# 3S2Pcard.net
KiCad netlist of a schematic drawn in EAGLE
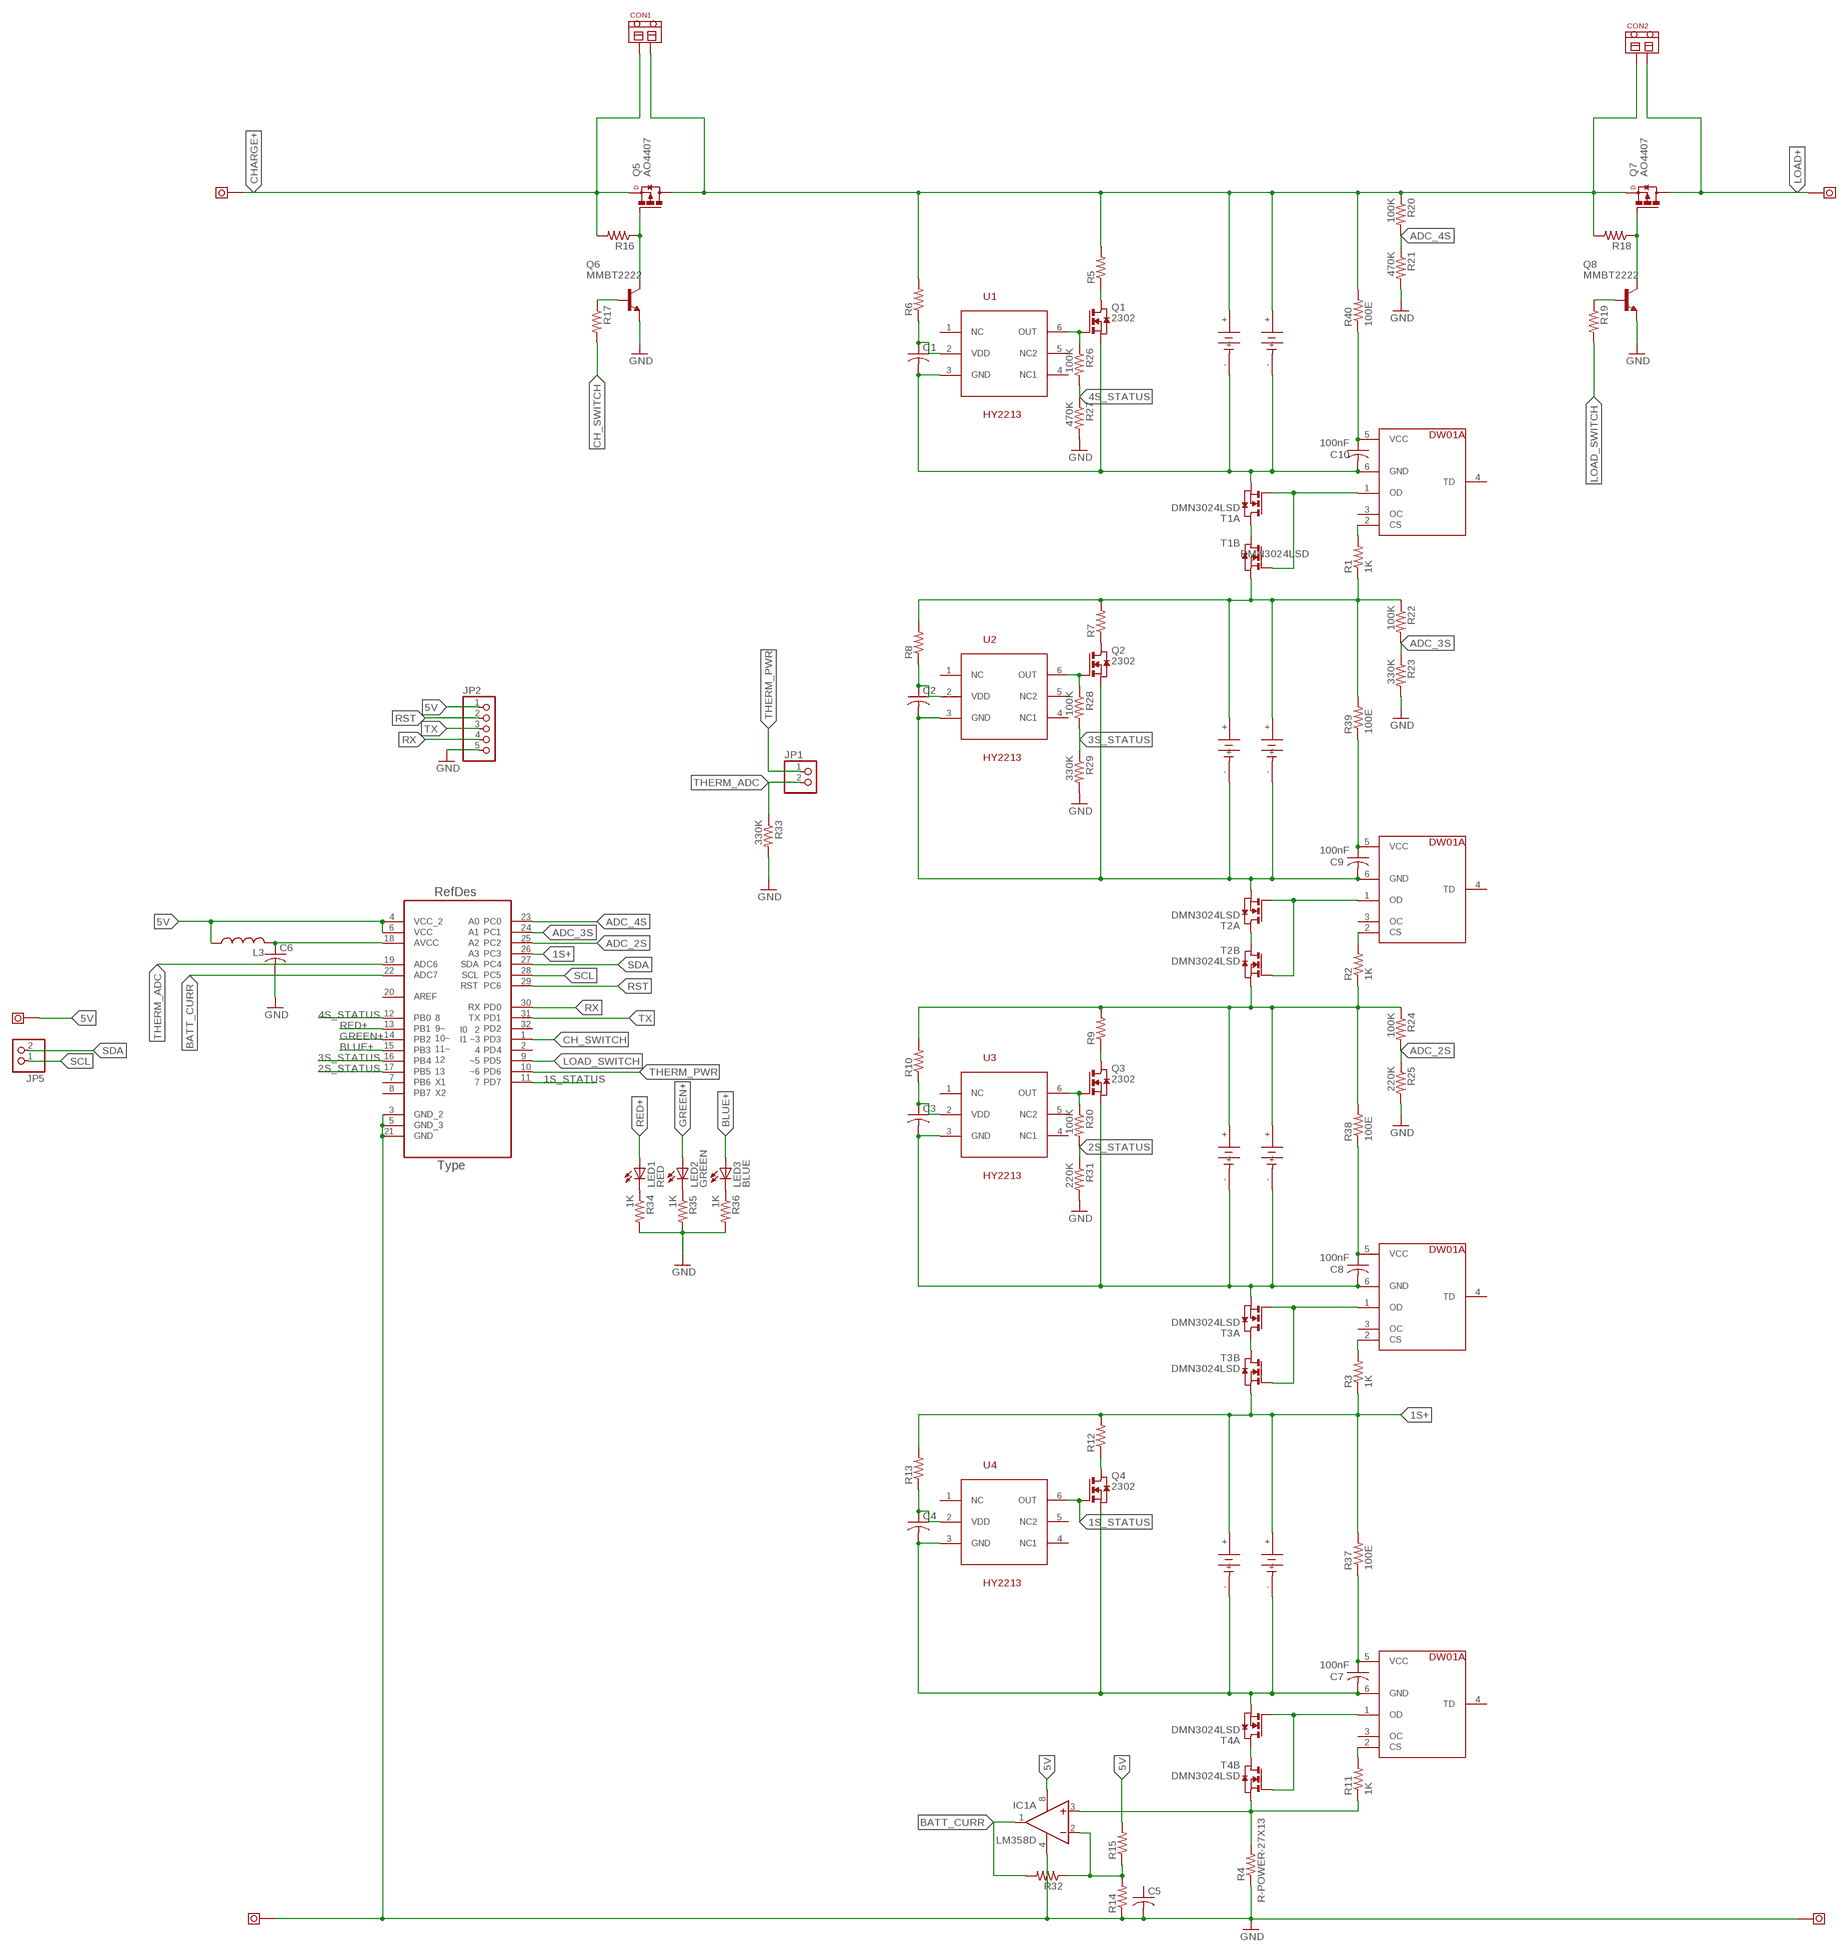
[diagram p0: schematic, sheet 1]

(export (version "E")
  (design (tool "Eeschema 10.0.6"))
  (components
    (comp (ref "B11")
      (value "18650_HOLDER")
      (footprint "eagle-import:18650_HOLDER")
      (libsource (lib "eagle-import") (part "18650_HOLDER"))
    )
    (comp (ref "B12")
      (value "18650_HOLDER")
      (footprint "eagle-import:18650_HOLDER")
      (libsource (lib "eagle-import") (part "18650_HOLDER"))
    )
    (comp (ref "B21")
      (value "18650_HOLDER")
      (footprint "eagle-import:18650_HOLDER")
      (libsource (lib "eagle-import") (part "18650_HOLDER"))
    )
    (comp (ref "B22")
      (value "18650_HOLDER")
      (footprint "eagle-import:18650_HOLDER")
      (libsource (lib "eagle-import") (part "18650_HOLDER"))
    )
    (comp (ref "B31")
      (value "18650_HOLDER")
      (footprint "eagle-import:18650_HOLDER")
      (libsource (lib "eagle-import") (part "18650_HOLDER"))
    )
    (comp (ref "B32")
      (value "18650_HOLDER")
      (footprint "eagle-import:18650_HOLDER")
      (libsource (lib "eagle-import") (part "18650_HOLDER"))
    )
    (comp (ref "B41")
      (value "18650_HOLDER")
      (footprint "eagle-import:18650_HOLDER")
      (libsource (lib "eagle-import") (part "18650_HOLDER"))
    )
    (comp (ref "B42")
      (value "18650_HOLDER")
      (footprint "eagle-import:18650_HOLDER")
      (libsource (lib "eagle-import") (part "18650_HOLDER"))
    )
    (comp (ref "C1")
      (value "C-USC0805")
      (footprint "eagle-import:C0805")
      (libsource (lib "eagle-import") (part "C-USC0805"))
    )
    (comp (ref "C2")
      (value "C-USC0805")
      (footprint "eagle-import:C0805")
      (libsource (lib "eagle-import") (part "C-USC0805"))
    )
    (comp (ref "C3")
      (value "C-USC0805")
      (footprint "eagle-import:C0805")
      (libsource (lib "eagle-import") (part "C-USC0805"))
    )
    (comp (ref "C4")
      (value "C-USC0805")
      (footprint "eagle-import:C0805")
      (libsource (lib "eagle-import") (part "C-USC0805"))
    )
    (comp (ref "C5")
      (value "C-USC0805")
      (footprint "eagle-import:C0805")
      (libsource (lib "eagle-import") (part "C-USC0805"))
    )
    (comp (ref "C6")
      (value "C-USC0805")
      (footprint "eagle-import:C0805")
      (libsource (lib "eagle-import") (part "C-USC0805"))
    )
    (comp (ref "C7")
      (value "100nF")
      (footprint "eagle-import:C0805")
      (libsource (lib "eagle-import") (part "C-USC0805"))
    )
    (comp (ref "C8")
      (value "100nF")
      (footprint "eagle-import:C0805")
      (libsource (lib "eagle-import") (part "C-USC0805"))
    )
    (comp (ref "C9")
      (value "100nF")
      (footprint "eagle-import:C0805")
      (libsource (lib "eagle-import") (part "C-USC0805"))
    )
    (comp (ref "C10")
      (value "100nF")
      (footprint "eagle-import:C0805")
      (libsource (lib "eagle-import") (part "C-USC0805"))
    )
    (comp (ref "CON1")
      (value "TERMINAL-SMALL")
      (footprint "eagle-import:TERMINAL-SMALL")
      (libsource (lib "eagle-import") (part "TERMINAL-SMALL"))
    )
    (comp (ref "CON2")
      (value "TERMINAL-SMALL")
      (footprint "eagle-import:TERMINAL-SMALL")
      (libsource (lib "eagle-import") (part "TERMINAL-SMALL"))
    )
    (comp (ref "IC1")
      (value "LM358D")
      (footprint "eagle-import:SO08")
      (libsource (lib "eagle-import") (part "LM358D"))
    )
    (comp (ref "JP1")
      (value "PINHD-1X2")
      (footprint "eagle-import:1X02")
      (libsource (lib "eagle-import") (part "PINHD-1X2"))
    )
    (comp (ref "JP2")
      (value "PINHD-1X5")
      (footprint "eagle-import:1X05")
      (libsource (lib "eagle-import") (part "PINHD-1X5"))
    )
    (comp (ref "JP5")
      (value "PINHD-1X2")
      (footprint "eagle-import:1X02")
      (libsource (lib "eagle-import") (part "PINHD-1X2"))
    )
    (comp (ref "L3")
      (value "L-US0207/10")
      (footprint "eagle-import:0207_10")
      (libsource (lib "eagle-import") (part "L-US0207/10"))
    )
    (comp (ref "LED1")
      (value "RED")
      (footprint "eagle-import:CHIP-LED0805")
      (libsource (lib "eagle-import") (part "LEDCHIP-LED0805"))
    )
    (comp (ref "LED2")
      (value "GREEN")
      (footprint "eagle-import:CHIP-LED0805")
      (libsource (lib "eagle-import") (part "LEDCHIP-LED0805"))
    )
    (comp (ref "LED3")
      (value "BLUE")
      (footprint "eagle-import:CHIP-LED0805")
      (libsource (lib "eagle-import") (part "LEDCHIP-LED0805"))
    )
    (comp (ref "Q1")
      (value "2302")
      (footprint "eagle-import:TO236")
      (libsource (lib "eagle-import") (part "2302"))
    )
    (comp (ref "Q2")
      (value "2302")
      (footprint "eagle-import:TO236")
      (libsource (lib "eagle-import") (part "2302"))
    )
    (comp (ref "Q3")
      (value "2302")
      (footprint "eagle-import:TO236")
      (libsource (lib "eagle-import") (part "2302"))
    )
    (comp (ref "Q4")
      (value "2302")
      (footprint "eagle-import:TO236")
      (libsource (lib "eagle-import") (part "2302"))
    )
    (comp (ref "Q5")
      (value "AO4407")
      (footprint "eagle-import:SOIC8")
      (libsource (lib "eagle-import") (part "AO4407"))
    )
    (comp (ref "Q6")
      (value "MMBT2222")
      (footprint "eagle-import:SOT-23-CBE")
      (libsource (lib "eagle-import") (part "MMBT2222"))
    )
    (comp (ref "Q7")
      (value "AO4407")
      (footprint "eagle-import:SOIC8")
      (libsource (lib "eagle-import") (part "AO4407"))
    )
    (comp (ref "Q8")
      (value "MMBT2222")
      (footprint "eagle-import:SOT-23-CBE")
      (libsource (lib "eagle-import") (part "MMBT2222"))
    )
    (comp (ref "R1")
      (value "1K")
      (footprint "eagle-import:R0805")
      (libsource (lib "eagle-import") (part "R-US_R0805"))
    )
    (comp (ref "R2")
      (value "1K")
      (footprint "eagle-import:R0805")
      (libsource (lib "eagle-import") (part "R-US_R0805"))
    )
    (comp (ref "R3")
      (value "1K")
      (footprint "eagle-import:R0805")
      (libsource (lib "eagle-import") (part "R-US_R0805"))
    )
    (comp (ref "R4")
      (value "R-POWER-27X13")
      (footprint "eagle-import:R-27X13")
      (libsource (lib "eagle-import") (part "R-POWER-27X13"))
    )
    (comp (ref "R5")
      (value "R-US_R1206W")
      (footprint "eagle-import:R1206W")
      (libsource (lib "eagle-import") (part "R-US_R1206W"))
    )
    (comp (ref "R6")
      (value "R-US_R0805")
      (footprint "eagle-import:R0805")
      (libsource (lib "eagle-import") (part "R-US_R0805"))
    )
    (comp (ref "R7")
      (value "R-US_R1206W")
      (footprint "eagle-import:R1206W")
      (libsource (lib "eagle-import") (part "R-US_R1206W"))
    )
    (comp (ref "R8")
      (value "R-US_R0805")
      (footprint "eagle-import:R0805")
      (libsource (lib "eagle-import") (part "R-US_R0805"))
    )
    (comp (ref "R9")
      (value "R-US_R1206W")
      (footprint "eagle-import:R1206W")
      (libsource (lib "eagle-import") (part "R-US_R1206W"))
    )
    (comp (ref "R10")
      (value "R-US_R0805")
      (footprint "eagle-import:R0805")
      (libsource (lib "eagle-import") (part "R-US_R0805"))
    )
    (comp (ref "R11")
      (value "1K")
      (footprint "eagle-import:R0805")
      (libsource (lib "eagle-import") (part "R-US_R0805"))
    )
    (comp (ref "R12")
      (value "R-US_R1206W")
      (footprint "eagle-import:R1206W")
      (libsource (lib "eagle-import") (part "R-US_R1206W"))
    )
    (comp (ref "R13")
      (value "R-US_R0805")
      (footprint "eagle-import:R0805")
      (libsource (lib "eagle-import") (part "R-US_R0805"))
    )
    (comp (ref "R14")
      (value "R-US_R0805")
      (footprint "eagle-import:R0805")
      (libsource (lib "eagle-import") (part "R-US_R0805"))
    )
    (comp (ref "R15")
      (value "R-US_R0805")
      (footprint "eagle-import:R0805")
      (libsource (lib "eagle-import") (part "R-US_R0805"))
    )
    (comp (ref "R16")
      (value "R-US_R0805")
      (footprint "eagle-import:R0805")
      (libsource (lib "eagle-import") (part "R-US_R0805"))
    )
    (comp (ref "R17")
      (value "R-US_R0805")
      (footprint "eagle-import:R0805")
      (libsource (lib "eagle-import") (part "R-US_R0805"))
    )
    (comp (ref "R18")
      (value "R-US_R0805")
      (footprint "eagle-import:R0805")
      (libsource (lib "eagle-import") (part "R-US_R0805"))
    )
    (comp (ref "R19")
      (value "R-US_R0805")
      (footprint "eagle-import:R0805")
      (libsource (lib "eagle-import") (part "R-US_R0805"))
    )
    (comp (ref "R20")
      (value "100K")
      (footprint "eagle-import:R0805")
      (libsource (lib "eagle-import") (part "R-US_R0805"))
    )
    (comp (ref "R21")
      (value "470K")
      (footprint "eagle-import:R0805")
      (libsource (lib "eagle-import") (part "R-US_R0805"))
    )
    (comp (ref "R22")
      (value "100K")
      (footprint "eagle-import:R0805")
      (libsource (lib "eagle-import") (part "R-US_R0805"))
    )
    (comp (ref "R23")
      (value "330K")
      (footprint "eagle-import:R0805")
      (libsource (lib "eagle-import") (part "R-US_R0805"))
    )
    (comp (ref "R24")
      (value "100K")
      (footprint "eagle-import:R0805")
      (libsource (lib "eagle-import") (part "R-US_R0805"))
    )
    (comp (ref "R25")
      (value "220K")
      (footprint "eagle-import:R0805")
      (libsource (lib "eagle-import") (part "R-US_R0805"))
    )
    (comp (ref "R26")
      (value "100K")
      (footprint "eagle-import:R0805")
      (libsource (lib "eagle-import") (part "R-US_R0805"))
    )
    (comp (ref "R27")
      (value "470K")
      (footprint "eagle-import:R0805")
      (libsource (lib "eagle-import") (part "R-US_R0805"))
    )
    (comp (ref "R28")
      (value "100K")
      (footprint "eagle-import:R0805")
      (libsource (lib "eagle-import") (part "R-US_R0805"))
    )
    (comp (ref "R29")
      (value "330K")
      (footprint "eagle-import:R0805")
      (libsource (lib "eagle-import") (part "R-US_R0805"))
    )
    (comp (ref "R30")
      (value "100K")
      (footprint "eagle-import:R0805")
      (libsource (lib "eagle-import") (part "R-US_R0805"))
    )
    (comp (ref "R31")
      (value "220K")
      (footprint "eagle-import:R0805")
      (libsource (lib "eagle-import") (part "R-US_R0805"))
    )
    (comp (ref "R32")
      (value "R-US_R0805")
      (footprint "eagle-import:R0805")
      (libsource (lib "eagle-import") (part "R-US_R0805"))
    )
    (comp (ref "R33")
      (value "330K")
      (footprint "eagle-import:R0805")
      (libsource (lib "eagle-import") (part "R-US_R0805"))
    )
    (comp (ref "R34")
      (value "1K")
      (footprint "eagle-import:R0805")
      (libsource (lib "eagle-import") (part "R-US_R0805"))
    )
    (comp (ref "R35")
      (value "1K")
      (footprint "eagle-import:R0805")
      (libsource (lib "eagle-import") (part "R-US_R0805"))
    )
    (comp (ref "R36")
      (value "1K")
      (footprint "eagle-import:R0805")
      (libsource (lib "eagle-import") (part "R-US_R0805"))
    )
    (comp (ref "R37")
      (value "100E")
      (footprint "eagle-import:R0805")
      (libsource (lib "eagle-import") (part "R-US_R0805"))
    )
    (comp (ref "R38")
      (value "100E")
      (footprint "eagle-import:R0805")
      (libsource (lib "eagle-import") (part "R-US_R0805"))
    )
    (comp (ref "R39")
      (value "100E")
      (footprint "eagle-import:R0805")
      (libsource (lib "eagle-import") (part "R-US_R0805"))
    )
    (comp (ref "R40")
      (value "100E")
      (footprint "eagle-import:R0805")
      (libsource (lib "eagle-import") (part "R-US_R0805"))
    )
    (comp (ref "T1")
      (value "DMN3024LSD")
      (footprint "eagle-import:TSSOP-8")
      (libsource (lib "eagle-import") (part "DMN3024LSD"))
    )
    (comp (ref "T2")
      (value "DMN3024LSD")
      (footprint "eagle-import:TSSOP-8")
      (libsource (lib "eagle-import") (part "DMN3024LSD"))
    )
    (comp (ref "T3")
      (value "DMN3024LSD")
      (footprint "eagle-import:TSSOP-8")
      (libsource (lib "eagle-import") (part "DMN3024LSD"))
    )
    (comp (ref "T4")
      (value "DMN3024LSD")
      (footprint "eagle-import:TSSOP-8")
      (libsource (lib "eagle-import") (part "DMN3024LSD"))
    )
    (comp (ref "U$7")
      (value "DW01A")
      (footprint "eagle-import:SOT23-6")
      (libsource (lib "eagle-import") (part "DW01A"))
    )
    (comp (ref "U$8")
      (value "DW01A")
      (footprint "eagle-import:SOT23-6")
      (libsource (lib "eagle-import") (part "DW01A"))
    )
    (comp (ref "U$9")
      (value "DW01A")
      (footprint "eagle-import:SOT23-6")
      (libsource (lib "eagle-import") (part "DW01A"))
    )
    (comp (ref "U$13")
      (value "METAL_SPACER")
      (footprint "eagle-import:SPACER")
      (libsource (lib "eagle-import") (part "METAL_SPACER"))
    )
    (comp (ref "U$14")
      (value "METAL_SPACER")
      (footprint "eagle-import:SPACER")
      (libsource (lib "eagle-import") (part "METAL_SPACER"))
    )
    (comp (ref "U$15")
      (value "METAL_SPACER")
      (footprint "eagle-import:SPACER")
      (libsource (lib "eagle-import") (part "METAL_SPACER"))
    )
    (comp (ref "U$16")
      (value "METAL_SPACER")
      (footprint "eagle-import:SPACER")
      (libsource (lib "eagle-import") (part "METAL_SPACER"))
    )
    (comp (ref "U$17")
      (value "METAL_SPACER")
      (footprint "eagle-import:SPACER")
      (libsource (lib "eagle-import") (part "METAL_SPACER"))
    )
    (comp (ref "U1")
      (value "HY2213")
      (footprint "eagle-import:SOT23-6")
      (libsource (lib "eagle-import") (part "HY2213"))
    )
    (comp (ref "U2")
      (value "HY2213")
      (footprint "eagle-import:SOT23-6")
      (libsource (lib "eagle-import") (part "HY2213"))
    )
    (comp (ref "U3")
      (value "HY2213")
      (footprint "eagle-import:SOT23-6")
      (libsource (lib "eagle-import") (part "HY2213"))
    )
    (comp (ref "U4")
      (value "HY2213")
      (footprint "eagle-import:SOT23-6")
      (libsource (lib "eagle-import") (part "HY2213"))
    )
    (comp (ref "U5")
      (value "ATMEGA328P-AU")
      (footprint "eagle-import:QFP80P900X900X120-32N")
      (libsource (lib "eagle-import") (part "ATMEGA328P-AU"))
    )
    (comp (ref "U12")
      (value "DW01A")
      (footprint "eagle-import:SOT23-6")
      (libsource (lib "eagle-import") (part "DW01A"))
    )
  )
  (nets
    (net (code "1") (name "1S+") (class "Default")
      (node (ref "B11") (pin "+") (pinfunction "+_+") (pintype "bidirectional"))
      (node (ref "B12") (pin "+") (pinfunction "+_+") (pintype "bidirectional"))
      (node (ref "R12") (pin "2") (pinfunction "2_2") (pintype "passive"))
      (node (ref "R13") (pin "2") (pinfunction "2_2") (pintype "passive"))
      (node (ref "R3") (pin "1") (pinfunction "1_1") (pintype "passive"))
      (node (ref "R37") (pin "2") (pinfunction "2_2") (pintype "passive"))
      (node (ref "T3") (pin "6") (pinfunction "S_6") (pintype "passive"))
      (node (ref "T3") (pin "7") (pinfunction "S_7") (pintype "passive"))
      (node (ref "U5") (pin "26") (pinfunction "PC3_26") (pintype "bidirectional"))
    )
    (net (code "2") (name "1S_STATUS") (class "Default")
      (node (ref "Q4") (pin "2") (pinfunction "G_2") (pintype "passive"))
      (node (ref "U4") (pin "6") (pinfunction "OUT_6") (pintype "bidirectional"))
      (node (ref "U5") (pin "11") (pinfunction "PD7_11") (pintype "bidirectional"))
    )
    (net (code "3") (name "2S_STATUS") (class "Default")
      (node (ref "R30") (pin "2") (pinfunction "2_2") (pintype "passive"))
      (node (ref "R31") (pin "1") (pinfunction "1_1") (pintype "passive"))
      (node (ref "U5") (pin "17") (pinfunction "PB5_17") (pintype "bidirectional"))
    )
    (net (code "4") (name "3S_STATUS") (class "Default")
      (node (ref "R28") (pin "2") (pinfunction "2_2") (pintype "passive"))
      (node (ref "R29") (pin "1") (pinfunction "1_1") (pintype "passive"))
      (node (ref "U5") (pin "16") (pinfunction "PB4_16") (pintype "bidirectional"))
    )
    (net (code "5") (name "4S_STATUS") (class "Default")
      (node (ref "R26") (pin "2") (pinfunction "2_2") (pintype "passive"))
      (node (ref "R27") (pin "1") (pinfunction "1_1") (pintype "passive"))
      (node (ref "U5") (pin "12") (pinfunction "PB0_12") (pintype "bidirectional"))
    )
    (net (code "6") (name "5V") (class "Default")
      (node (ref "IC1") (pin "8") (pinfunction "V+_8") (pintype "power_in"))
      (node (ref "JP2") (pin "1") (pinfunction "1_1") (pintype "passive"))
      (node (ref "L3") (pin "1") (pinfunction "1_1") (pintype "passive"))
      (node (ref "R15") (pin "2") (pinfunction "2_2") (pintype "passive"))
      (node (ref "U$17") (pin "1") (pinfunction "P$1_1") (pintype "bidirectional"))
      (node (ref "U5") (pin "4") (pinfunction "VCC_2_4") (pintype "power_in"))
      (node (ref "U5") (pin "6") (pinfunction "VCC_6") (pintype "power_in"))
    )
    (net (code "7") (name "ADC_2S") (class "Default")
      (node (ref "R24") (pin "2") (pinfunction "2_2") (pintype "passive"))
      (node (ref "R25") (pin "1") (pinfunction "1_1") (pintype "passive"))
      (node (ref "U5") (pin "25") (pinfunction "PC2_25") (pintype "bidirectional"))
    )
    (net (code "8") (name "ADC_3S") (class "Default")
      (node (ref "R22") (pin "2") (pinfunction "2_2") (pintype "passive"))
      (node (ref "R23") (pin "1") (pinfunction "1_1") (pintype "passive"))
      (node (ref "U5") (pin "24") (pinfunction "PC1_24") (pintype "bidirectional"))
    )
    (net (code "9") (name "ADC_4S") (class "Default")
      (node (ref "R20") (pin "2") (pinfunction "2_2") (pintype "passive"))
      (node (ref "R21") (pin "1") (pinfunction "1_1") (pintype "passive"))
      (node (ref "U5") (pin "23") (pinfunction "PC0_23") (pintype "bidirectional"))
    )
    (net (code "10") (name "BATT_CURR") (class "Default")
      (node (ref "IC1") (pin "1") (pinfunction "OUT_1") (pintype "output"))
      (node (ref "R32") (pin "2") (pinfunction "2_2") (pintype "passive"))
      (node (ref "U5") (pin "22") (pinfunction "ADC7_22") (pintype "input"))
    )
    (net (code "11") (name "BLUE+") (class "Default")
      (node (ref "LED3") (pin "A") (pinfunction "A_A") (pintype "passive"))
      (node (ref "U5") (pin "15") (pinfunction "PB3_15") (pintype "bidirectional"))
    )
    (net (code "12") (name "CHARGE+") (class "Default")
      (node (ref "CON1") (pin "1") (pinfunction "1_1") (pintype "bidirectional"))
      (node (ref "Q5") (pin "5") (pinfunction "D_5") (pintype "passive"))
      (node (ref "Q5") (pin "6") (pinfunction "D_6") (pintype "passive"))
      (node (ref "Q5") (pin "7") (pinfunction "D_7") (pintype "passive"))
      (node (ref "Q5") (pin "8") (pinfunction "D_8") (pintype "passive"))
      (node (ref "R16") (pin "2") (pinfunction "2_2") (pintype "passive"))
      (node (ref "U$15") (pin "1") (pinfunction "P$1_1") (pintype "bidirectional"))
    )
    (net (code "13") (name "CH_SWITCH") (class "Default")
      (node (ref "R17") (pin "2") (pinfunction "2_2") (pintype "passive"))
      (node (ref "U5") (pin "1") (pinfunction "PD3_1") (pintype "bidirectional"))
    )
    (net (code "14") (name "GND") (class "Default")
      (node (ref "C5") (pin "2") (pinfunction "2_2") (pintype "passive"))
      (node (ref "C6") (pin "2") (pinfunction "2_2") (pintype "passive"))
      (node (ref "IC1") (pin "4") (pinfunction "V-_4") (pintype "power_in"))
      (node (ref "JP2") (pin "5") (pinfunction "5_5") (pintype "passive"))
      (node (ref "Q6") (pin "E") (pinfunction "E_E") (pintype "passive"))
      (node (ref "Q8") (pin "E") (pinfunction "E_E") (pintype "passive"))
      (node (ref "R14") (pin "1") (pinfunction "1_1") (pintype "passive"))
      (node (ref "R21") (pin "2") (pinfunction "2_2") (pintype "passive"))
      (node (ref "R23") (pin "2") (pinfunction "2_2") (pintype "passive"))
      (node (ref "R25") (pin "2") (pinfunction "2_2") (pintype "passive"))
      (node (ref "R27") (pin "2") (pinfunction "2_2") (pintype "passive"))
      (node (ref "R29") (pin "2") (pinfunction "2_2") (pintype "passive"))
      (node (ref "R31") (pin "2") (pinfunction "2_2") (pintype "passive"))
      (node (ref "R33") (pin "2") (pinfunction "2_2") (pintype "passive"))
      (node (ref "R34") (pin "2") (pinfunction "2_2") (pintype "passive"))
      (node (ref "R35") (pin "2") (pinfunction "2_2") (pintype "passive"))
      (node (ref "R36") (pin "2") (pinfunction "2_2") (pintype "passive"))
      (node (ref "R4") (pin "1") (pinfunction "1_1") (pintype "passive"))
      (node (ref "U$14") (pin "1") (pinfunction "P$1_1") (pintype "bidirectional"))
      (node (ref "U$16") (pin "1") (pinfunction "P$1_1") (pintype "bidirectional"))
      (node (ref "U5") (pin "21") (pinfunction "GND_21") (pintype "passive"))
      (node (ref "U5") (pin "3") (pinfunction "GND_2_3") (pintype "passive"))
      (node (ref "U5") (pin "5") (pinfunction "GND_3_5") (pintype "passive"))
    )
    (net (code "15") (name "GREEN+") (class "Default")
      (node (ref "LED2") (pin "A") (pinfunction "A_A") (pintype "passive"))
      (node (ref "U5") (pin "14") (pinfunction "PB2_14") (pintype "bidirectional"))
    )
    (net (code "16") (name "LOAD+") (class "Default")
      (node (ref "CON2") (pin "2") (pinfunction "2_2") (pintype "bidirectional"))
      (node (ref "Q7") (pin "1") (pinfunction "S_1") (pintype "passive"))
      (node (ref "Q7") (pin "2") (pinfunction "S_2") (pintype "passive"))
      (node (ref "Q7") (pin "3") (pinfunction "S_3") (pintype "passive"))
      (node (ref "U$13") (pin "1") (pinfunction "P$1_1") (pintype "bidirectional"))
    )
    (net (code "17") (name "LOAD_SWITCH") (class "Default")
      (node (ref "R19") (pin "2") (pinfunction "2_2") (pintype "passive"))
      (node (ref "U5") (pin "9") (pinfunction "PD5_9") (pintype "bidirectional"))
    )
    (net (code "18") (name "Net-(B21-Pad+)") (class "Default")
      (node (ref "B21") (pin "+") (pinfunction "+_+") (pintype "bidirectional"))
      (node (ref "B22") (pin "+") (pinfunction "+_+") (pintype "bidirectional"))
      (node (ref "R10") (pin "2") (pinfunction "2_2") (pintype "passive"))
      (node (ref "R2") (pin "1") (pinfunction "1_1") (pintype "passive"))
      (node (ref "R24") (pin "1") (pinfunction "1_1") (pintype "passive"))
      (node (ref "R38") (pin "2") (pinfunction "2_2") (pintype "passive"))
      (node (ref "R9") (pin "2") (pinfunction "2_2") (pintype "passive"))
      (node (ref "T2") (pin "6") (pinfunction "S_6") (pintype "passive"))
      (node (ref "T2") (pin "7") (pinfunction "S_7") (pintype "passive"))
    )
    (net (code "19") (name "Net-(B31-Pad+)") (class "Default")
      (node (ref "B31") (pin "+") (pinfunction "+_+") (pintype "bidirectional"))
      (node (ref "B32") (pin "+") (pinfunction "+_+") (pintype "bidirectional"))
      (node (ref "R1") (pin "1") (pinfunction "1_1") (pintype "passive"))
      (node (ref "R22") (pin "1") (pinfunction "1_1") (pintype "passive"))
      (node (ref "R39") (pin "2") (pinfunction "2_2") (pintype "passive"))
      (node (ref "R7") (pin "2") (pinfunction "2_2") (pintype "passive"))
      (node (ref "R8") (pin "2") (pinfunction "2_2") (pintype "passive"))
      (node (ref "T1") (pin "6") (pinfunction "S_6") (pintype "passive"))
      (node (ref "T1") (pin "7") (pinfunction "S_7") (pintype "passive"))
    )
    (net (code "20") (name "Net-(B41-Pad+)") (class "Default")
      (node (ref "B41") (pin "+") (pinfunction "+_+") (pintype "bidirectional"))
      (node (ref "B42") (pin "+") (pinfunction "+_+") (pintype "bidirectional"))
      (node (ref "CON1") (pin "2") (pinfunction "2_2") (pintype "bidirectional"))
      (node (ref "CON2") (pin "1") (pinfunction "1_1") (pintype "bidirectional"))
      (node (ref "Q5") (pin "1") (pinfunction "S_1") (pintype "passive"))
      (node (ref "Q5") (pin "2") (pinfunction "S_2") (pintype "passive"))
      (node (ref "Q5") (pin "3") (pinfunction "S_3") (pintype "passive"))
      (node (ref "Q7") (pin "5") (pinfunction "D_5") (pintype "passive"))
      (node (ref "Q7") (pin "6") (pinfunction "D_6") (pintype "passive"))
      (node (ref "Q7") (pin "7") (pinfunction "D_7") (pintype "passive"))
      (node (ref "Q7") (pin "8") (pinfunction "D_8") (pintype "passive"))
      (node (ref "R18") (pin "2") (pinfunction "2_2") (pintype "passive"))
      (node (ref "R20") (pin "1") (pinfunction "1_1") (pintype "passive"))
      (node (ref "R40") (pin "2") (pinfunction "2_2") (pintype "passive"))
      (node (ref "R5") (pin "2") (pinfunction "2_2") (pintype "passive"))
      (node (ref "R6") (pin "2") (pinfunction "2_2") (pintype "passive"))
    )
    (net (code "21") (name "Net-(IC1A-+IN)") (class "Default")
      (node (ref "IC1") (pin "3") (pinfunction "+IN_3") (pintype "input"))
      (node (ref "R11") (pin "1") (pinfunction "1_1") (pintype "passive"))
      (node (ref "R4") (pin "2") (pinfunction "2_2") (pintype "passive"))
      (node (ref "T4") (pin "6") (pinfunction "S_6") (pintype "passive"))
      (node (ref "T4") (pin "7") (pinfunction "S_7") (pintype "passive"))
    )
    (net (code "22") (name "Net-(IC1A--IN)") (class "Default")
      (node (ref "IC1") (pin "2") (pinfunction "-IN_2") (pintype "input"))
      (node (ref "R14") (pin "2") (pinfunction "2_2") (pintype "passive"))
      (node (ref "R15") (pin "1") (pinfunction "1_1") (pintype "passive"))
      (node (ref "R32") (pin "1") (pinfunction "1_1") (pintype "passive"))
    )
    (net (code "23") (name "Net-(LED1-PadC)") (class "Default")
      (node (ref "LED1") (pin "C") (pinfunction "C_C") (pintype "passive"))
      (node (ref "R34") (pin "1") (pinfunction "1_1") (pintype "passive"))
    )
    (net (code "24") (name "Net-(LED2-PadC)") (class "Default")
      (node (ref "LED2") (pin "C") (pinfunction "C_C") (pintype "passive"))
      (node (ref "R35") (pin "1") (pinfunction "1_1") (pintype "passive"))
    )
    (net (code "25") (name "Net-(LED3-PadC)") (class "Default")
      (node (ref "LED3") (pin "C") (pinfunction "C_C") (pintype "passive"))
      (node (ref "R36") (pin "1") (pinfunction "1_1") (pintype "passive"))
    )
    (net (code "26") (name "Net-(Q1-D)") (class "Default")
      (node (ref "Q1") (pin "1") (pinfunction "D_1") (pintype "passive"))
      (node (ref "R5") (pin "1") (pinfunction "1_1") (pintype "passive"))
    )
    (net (code "27") (name "Net-(Q1-G)") (class "Default")
      (node (ref "Q1") (pin "2") (pinfunction "G_2") (pintype "passive"))
      (node (ref "R26") (pin "1") (pinfunction "1_1") (pintype "passive"))
      (node (ref "U1") (pin "6") (pinfunction "OUT_6") (pintype "bidirectional"))
    )
    (net (code "28") (name "Net-(Q1-S)") (class "Default")
      (node (ref "B41") (pin "-") (pinfunction "-_-") (pintype "bidirectional"))
      (node (ref "B42") (pin "-") (pinfunction "-_-") (pintype "bidirectional"))
      (node (ref "C1") (pin "2") (pinfunction "2_2") (pintype "passive"))
      (node (ref "C10") (pin "2") (pinfunction "2_2") (pintype "passive"))
      (node (ref "Q1") (pin "3") (pinfunction "S_3") (pintype "passive"))
      (node (ref "T1") (pin "2") (pinfunction "S_2") (pintype "passive"))
      (node (ref "T1") (pin "3") (pinfunction "S_3") (pintype "passive"))
      (node (ref "U$7") (pin "6") (pinfunction "GND_6") (pintype "bidirectional"))
      (node (ref "U1") (pin "3") (pinfunction "GND_3") (pintype "bidirectional"))
    )
    (net (code "29") (name "Net-(Q2-D)") (class "Default")
      (node (ref "Q2") (pin "1") (pinfunction "D_1") (pintype "passive"))
      (node (ref "R7") (pin "1") (pinfunction "1_1") (pintype "passive"))
    )
    (net (code "30") (name "Net-(Q2-G)") (class "Default")
      (node (ref "Q2") (pin "2") (pinfunction "G_2") (pintype "passive"))
      (node (ref "R28") (pin "1") (pinfunction "1_1") (pintype "passive"))
      (node (ref "U2") (pin "6") (pinfunction "OUT_6") (pintype "bidirectional"))
    )
    (net (code "31") (name "Net-(Q2-S)") (class "Default")
      (node (ref "B31") (pin "-") (pinfunction "-_-") (pintype "bidirectional"))
      (node (ref "B32") (pin "-") (pinfunction "-_-") (pintype "bidirectional"))
      (node (ref "C2") (pin "2") (pinfunction "2_2") (pintype "passive"))
      (node (ref "C9") (pin "2") (pinfunction "2_2") (pintype "passive"))
      (node (ref "Q2") (pin "3") (pinfunction "S_3") (pintype "passive"))
      (node (ref "T2") (pin "2") (pinfunction "S_2") (pintype "passive"))
      (node (ref "T2") (pin "3") (pinfunction "S_3") (pintype "passive"))
      (node (ref "U$8") (pin "6") (pinfunction "GND_6") (pintype "bidirectional"))
      (node (ref "U2") (pin "3") (pinfunction "GND_3") (pintype "bidirectional"))
    )
    (net (code "32") (name "Net-(Q3-D)") (class "Default")
      (node (ref "Q3") (pin "1") (pinfunction "D_1") (pintype "passive"))
      (node (ref "R9") (pin "1") (pinfunction "1_1") (pintype "passive"))
    )
    (net (code "33") (name "Net-(Q3-G)") (class "Default")
      (node (ref "Q3") (pin "2") (pinfunction "G_2") (pintype "passive"))
      (node (ref "R30") (pin "1") (pinfunction "1_1") (pintype "passive"))
      (node (ref "U3") (pin "6") (pinfunction "OUT_6") (pintype "bidirectional"))
    )
    (net (code "34") (name "Net-(Q3-S)") (class "Default")
      (node (ref "B21") (pin "-") (pinfunction "-_-") (pintype "bidirectional"))
      (node (ref "B22") (pin "-") (pinfunction "-_-") (pintype "bidirectional"))
      (node (ref "C3") (pin "2") (pinfunction "2_2") (pintype "passive"))
      (node (ref "C8") (pin "2") (pinfunction "2_2") (pintype "passive"))
      (node (ref "Q3") (pin "3") (pinfunction "S_3") (pintype "passive"))
      (node (ref "T3") (pin "2") (pinfunction "S_2") (pintype "passive"))
      (node (ref "T3") (pin "3") (pinfunction "S_3") (pintype "passive"))
      (node (ref "U$9") (pin "6") (pinfunction "GND_6") (pintype "bidirectional"))
      (node (ref "U3") (pin "3") (pinfunction "GND_3") (pintype "bidirectional"))
    )
    (net (code "35") (name "Net-(Q4-D)") (class "Default")
      (node (ref "Q4") (pin "1") (pinfunction "D_1") (pintype "passive"))
      (node (ref "R12") (pin "1") (pinfunction "1_1") (pintype "passive"))
    )
    (net (code "36") (name "Net-(Q4-S)") (class "Default")
      (node (ref "B11") (pin "-") (pinfunction "-_-") (pintype "bidirectional"))
      (node (ref "B12") (pin "-") (pinfunction "-_-") (pintype "bidirectional"))
      (node (ref "C4") (pin "2") (pinfunction "2_2") (pintype "passive"))
      (node (ref "C7") (pin "2") (pinfunction "2_2") (pintype "passive"))
      (node (ref "Q4") (pin "3") (pinfunction "S_3") (pintype "passive"))
      (node (ref "T4") (pin "2") (pinfunction "S_2") (pintype "passive"))
      (node (ref "T4") (pin "3") (pinfunction "S_3") (pintype "passive"))
      (node (ref "U12") (pin "6") (pinfunction "GND_6") (pintype "bidirectional"))
      (node (ref "U4") (pin "3") (pinfunction "GND_3") (pintype "bidirectional"))
    )
    (net (code "37") (name "Net-(Q5-G)") (class "Default")
      (node (ref "Q5") (pin "4") (pinfunction "G_4") (pintype "passive"))
      (node (ref "Q6") (pin "C") (pinfunction "C_C") (pintype "passive"))
      (node (ref "R16") (pin "1") (pinfunction "1_1") (pintype "passive"))
    )
    (net (code "38") (name "Net-(Q6-PadB)") (class "Default")
      (node (ref "Q6") (pin "B") (pinfunction "B_B") (pintype "passive"))
      (node (ref "R17") (pin "1") (pinfunction "1_1") (pintype "passive"))
    )
    (net (code "39") (name "Net-(Q7-G)") (class "Default")
      (node (ref "Q7") (pin "4") (pinfunction "G_4") (pintype "passive"))
      (node (ref "Q8") (pin "C") (pinfunction "C_C") (pintype "passive"))
      (node (ref "R18") (pin "1") (pinfunction "1_1") (pintype "passive"))
    )
    (net (code "40") (name "Net-(Q8-PadB)") (class "Default")
      (node (ref "Q8") (pin "B") (pinfunction "B_B") (pintype "passive"))
      (node (ref "R19") (pin "1") (pinfunction "1_1") (pintype "passive"))
    )
    (net (code "41") (name "Net-(T1A-D)") (class "Default")
      (node (ref "T1") (pin "1") (pinfunction "D_1") (pintype "passive"))
      (node (ref "T1") (pin "8") (pinfunction "D_8") (pintype "passive"))
    )
    (net (code "42") (name "Net-(T1A-G)") (class "Default")
      (node (ref "T1") (pin "4") (pinfunction "G_4") (pintype "passive"))
      (node (ref "T1") (pin "5") (pinfunction "G_5") (pintype "passive"))
      (node (ref "U$7") (pin "1") (pinfunction "OD_1") (pintype "bidirectional"))
    )
    (net (code "43") (name "Net-(T2A-D)") (class "Default")
      (node (ref "T2") (pin "1") (pinfunction "D_1") (pintype "passive"))
      (node (ref "T2") (pin "8") (pinfunction "D_8") (pintype "passive"))
    )
    (net (code "44") (name "Net-(T2A-G)") (class "Default")
      (node (ref "T2") (pin "4") (pinfunction "G_4") (pintype "passive"))
      (node (ref "T2") (pin "5") (pinfunction "G_5") (pintype "passive"))
      (node (ref "U$8") (pin "1") (pinfunction "OD_1") (pintype "bidirectional"))
    )
    (net (code "45") (name "Net-(T3A-D)") (class "Default")
      (node (ref "T3") (pin "1") (pinfunction "D_1") (pintype "passive"))
      (node (ref "T3") (pin "8") (pinfunction "D_8") (pintype "passive"))
    )
    (net (code "46") (name "Net-(T3A-G)") (class "Default")
      (node (ref "T3") (pin "4") (pinfunction "G_4") (pintype "passive"))
      (node (ref "T3") (pin "5") (pinfunction "G_5") (pintype "passive"))
      (node (ref "U$9") (pin "1") (pinfunction "OD_1") (pintype "bidirectional"))
    )
    (net (code "47") (name "Net-(T4A-D)") (class "Default")
      (node (ref "T4") (pin "1") (pinfunction "D_1") (pintype "passive"))
      (node (ref "T4") (pin "8") (pinfunction "D_8") (pintype "passive"))
    )
    (net (code "48") (name "Net-(T4A-G)") (class "Default")
      (node (ref "T4") (pin "4") (pinfunction "G_4") (pintype "passive"))
      (node (ref "T4") (pin "5") (pinfunction "G_5") (pintype "passive"))
      (node (ref "U12") (pin "1") (pinfunction "OD_1") (pintype "bidirectional"))
    )
    (net (code "49") (name "Net-(U$7-CS)") (class "Default")
      (node (ref "R1") (pin "2") (pinfunction "2_2") (pintype "passive"))
      (node (ref "U$7") (pin "2") (pinfunction "CS_2") (pintype "bidirectional"))
    )
    (net (code "50") (name "Net-(U$7-VCC)") (class "Default")
      (node (ref "C10") (pin "1") (pinfunction "1_1") (pintype "passive"))
      (node (ref "R40") (pin "1") (pinfunction "1_1") (pintype "passive"))
      (node (ref "U$7") (pin "5") (pinfunction "VCC_5") (pintype "bidirectional"))
    )
    (net (code "51") (name "Net-(U$8-CS)") (class "Default")
      (node (ref "R2") (pin "2") (pinfunction "2_2") (pintype "passive"))
      (node (ref "U$8") (pin "2") (pinfunction "CS_2") (pintype "bidirectional"))
    )
    (net (code "52") (name "Net-(U$8-VCC)") (class "Default")
      (node (ref "C9") (pin "1") (pinfunction "1_1") (pintype "passive"))
      (node (ref "R39") (pin "1") (pinfunction "1_1") (pintype "passive"))
      (node (ref "U$8") (pin "5") (pinfunction "VCC_5") (pintype "bidirectional"))
    )
    (net (code "53") (name "Net-(U$9-CS)") (class "Default")
      (node (ref "R3") (pin "2") (pinfunction "2_2") (pintype "passive"))
      (node (ref "U$9") (pin "2") (pinfunction "CS_2") (pintype "bidirectional"))
    )
    (net (code "54") (name "Net-(U$9-VCC)") (class "Default")
      (node (ref "C8") (pin "1") (pinfunction "1_1") (pintype "passive"))
      (node (ref "R38") (pin "1") (pinfunction "1_1") (pintype "passive"))
      (node (ref "U$9") (pin "5") (pinfunction "VCC_5") (pintype "bidirectional"))
    )
    (net (code "55") (name "Net-(U1-VDD)") (class "Default")
      (node (ref "C1") (pin "1") (pinfunction "1_1") (pintype "passive"))
      (node (ref "R6") (pin "1") (pinfunction "1_1") (pintype "passive"))
      (node (ref "U1") (pin "2") (pinfunction "VDD_2") (pintype "bidirectional"))
    )
    (net (code "56") (name "Net-(U2-VDD)") (class "Default")
      (node (ref "C2") (pin "1") (pinfunction "1_1") (pintype "passive"))
      (node (ref "R8") (pin "1") (pinfunction "1_1") (pintype "passive"))
      (node (ref "U2") (pin "2") (pinfunction "VDD_2") (pintype "bidirectional"))
    )
    (net (code "57") (name "Net-(U3-VDD)") (class "Default")
      (node (ref "C3") (pin "1") (pinfunction "1_1") (pintype "passive"))
      (node (ref "R10") (pin "1") (pinfunction "1_1") (pintype "passive"))
      (node (ref "U3") (pin "2") (pinfunction "VDD_2") (pintype "bidirectional"))
    )
    (net (code "58") (name "Net-(U4-VDD)") (class "Default")
      (node (ref "C4") (pin "1") (pinfunction "1_1") (pintype "passive"))
      (node (ref "R13") (pin "1") (pinfunction "1_1") (pintype "passive"))
      (node (ref "U4") (pin "2") (pinfunction "VDD_2") (pintype "bidirectional"))
    )
    (net (code "59") (name "Net-(U5-AVCC)") (class "Default")
      (node (ref "C6") (pin "1") (pinfunction "1_1") (pintype "passive"))
      (node (ref "L3") (pin "2") (pinfunction "2_2") (pintype "passive"))
      (node (ref "U5") (pin "18") (pinfunction "AVCC_18") (pintype "power_in"))
    )
    (net (code "60") (name "Net-(U12-CS)") (class "Default")
      (node (ref "R11") (pin "2") (pinfunction "2_2") (pintype "passive"))
      (node (ref "U12") (pin "2") (pinfunction "CS_2") (pintype "bidirectional"))
    )
    (net (code "61") (name "Net-(U12-VCC)") (class "Default")
      (node (ref "C7") (pin "1") (pinfunction "1_1") (pintype "passive"))
      (node (ref "R37") (pin "1") (pinfunction "1_1") (pintype "passive"))
      (node (ref "U12") (pin "5") (pinfunction "VCC_5") (pintype "bidirectional"))
    )
    (net (code "62") (name "RED+") (class "Default")
      (node (ref "LED1") (pin "A") (pinfunction "A_A") (pintype "passive"))
      (node (ref "U5") (pin "13") (pinfunction "PB1_13") (pintype "bidirectional"))
    )
    (net (code "63") (name "RST") (class "Default")
      (node (ref "JP2") (pin "2") (pinfunction "2_2") (pintype "passive"))
      (node (ref "U5") (pin "29") (pinfunction "PC6_29") (pintype "bidirectional"))
    )
    (net (code "64") (name "RX") (class "Default")
      (node (ref "JP2") (pin "4") (pinfunction "4_4") (pintype "passive"))
      (node (ref "U5") (pin "30") (pinfunction "PD0_30") (pintype "bidirectional"))
    )
    (net (code "65") (name "SCL") (class "Default")
      (node (ref "JP5") (pin "1") (pinfunction "1_1") (pintype "passive"))
      (node (ref "U5") (pin "28") (pinfunction "PC5_28") (pintype "bidirectional"))
    )
    (net (code "66") (name "SDA") (class "Default")
      (node (ref "JP5") (pin "2") (pinfunction "2_2") (pintype "passive"))
      (node (ref "U5") (pin "27") (pinfunction "PC4_27") (pintype "bidirectional"))
    )
    (net (code "67") (name "THERM_ADC") (class "Default")
      (node (ref "JP1") (pin "2") (pinfunction "2_2") (pintype "passive"))
      (node (ref "R33") (pin "1") (pinfunction "1_1") (pintype "passive"))
      (node (ref "U5") (pin "19") (pinfunction "ADC6_19") (pintype "input"))
    )
    (net (code "68") (name "THERM_PWR") (class "Default")
      (node (ref "JP1") (pin "1") (pinfunction "1_1") (pintype "passive"))
      (node (ref "U5") (pin "10") (pinfunction "PD6_10") (pintype "bidirectional"))
    )
    (net (code "69") (name "TX") (class "Default")
      (node (ref "JP2") (pin "3") (pinfunction "3_3") (pintype "passive"))
      (node (ref "U5") (pin "31") (pinfunction "PD1_31") (pintype "bidirectional"))
    )
    (net (code "70") (name "unconnected-(C5-Pad1)") (class "Default")
      (node (ref "C5") (pin "1") (pinfunction "1_1") (pintype "passive"))
    )
    (net (code "71") (name "unconnected-(U$7-OC-Pad3)") (class "Default")
      (node (ref "U$7") (pin "3") (pinfunction "OC_3") (pintype "bidirectional"))
    )
    (net (code "72") (name "unconnected-(U$7-TD-Pad4)") (class "Default")
      (node (ref "U$7") (pin "4") (pinfunction "TD_4") (pintype "bidirectional"))
    )
    (net (code "73") (name "unconnected-(U$8-OC-Pad3)") (class "Default")
      (node (ref "U$8") (pin "3") (pinfunction "OC_3") (pintype "bidirectional"))
    )
    (net (code "74") (name "unconnected-(U$8-TD-Pad4)") (class "Default")
      (node (ref "U$8") (pin "4") (pinfunction "TD_4") (pintype "bidirectional"))
    )
    (net (code "75") (name "unconnected-(U$9-OC-Pad3)") (class "Default")
      (node (ref "U$9") (pin "3") (pinfunction "OC_3") (pintype "bidirectional"))
    )
    (net (code "76") (name "unconnected-(U$9-TD-Pad4)") (class "Default")
      (node (ref "U$9") (pin "4") (pinfunction "TD_4") (pintype "bidirectional"))
    )
    (net (code "77") (name "unconnected-(U1-NC-Pad1)") (class "Default")
      (node (ref "U1") (pin "1") (pinfunction "NC_1") (pintype "bidirectional"))
    )
    (net (code "78") (name "unconnected-(U1-NC1-Pad4)") (class "Default")
      (node (ref "U1") (pin "4") (pinfunction "NC1_4") (pintype "bidirectional"))
    )
    (net (code "79") (name "unconnected-(U1-NC2-Pad5)") (class "Default")
      (node (ref "U1") (pin "5") (pinfunction "NC2_5") (pintype "bidirectional"))
    )
    (net (code "80") (name "unconnected-(U2-NC-Pad1)") (class "Default")
      (node (ref "U2") (pin "1") (pinfunction "NC_1") (pintype "bidirectional"))
    )
    (net (code "81") (name "unconnected-(U2-NC1-Pad4)") (class "Default")
      (node (ref "U2") (pin "4") (pinfunction "NC1_4") (pintype "bidirectional"))
    )
    (net (code "82") (name "unconnected-(U2-NC2-Pad5)") (class "Default")
      (node (ref "U2") (pin "5") (pinfunction "NC2_5") (pintype "bidirectional"))
    )
    (net (code "83") (name "unconnected-(U3-NC-Pad1)") (class "Default")
      (node (ref "U3") (pin "1") (pinfunction "NC_1") (pintype "bidirectional"))
    )
    (net (code "84") (name "unconnected-(U3-NC1-Pad4)") (class "Default")
      (node (ref "U3") (pin "4") (pinfunction "NC1_4") (pintype "bidirectional"))
    )
    (net (code "85") (name "unconnected-(U3-NC2-Pad5)") (class "Default")
      (node (ref "U3") (pin "5") (pinfunction "NC2_5") (pintype "bidirectional"))
    )
    (net (code "86") (name "unconnected-(U4-NC-Pad1)") (class "Default")
      (node (ref "U4") (pin "1") (pinfunction "NC_1") (pintype "bidirectional"))
    )
    (net (code "87") (name "unconnected-(U4-NC1-Pad4)") (class "Default")
      (node (ref "U4") (pin "4") (pinfunction "NC1_4") (pintype "bidirectional"))
    )
    (net (code "88") (name "unconnected-(U4-NC2-Pad5)") (class "Default")
      (node (ref "U4") (pin "5") (pinfunction "NC2_5") (pintype "bidirectional"))
    )
    (net (code "89") (name "unconnected-(U5-AREF-Pad20)") (class "Default")
      (node (ref "U5") (pin "20") (pinfunction "AREF_20") (pintype "input"))
    )
    (net (code "90") (name "unconnected-(U5-PB6-Pad7)") (class "Default")
      (node (ref "U5") (pin "7") (pinfunction "PB6_7") (pintype "bidirectional"))
    )
    (net (code "91") (name "unconnected-(U5-PB7-Pad8)") (class "Default")
      (node (ref "U5") (pin "8") (pinfunction "PB7_8") (pintype "bidirectional"))
    )
    (net (code "92") (name "unconnected-(U5-PD2-Pad32)") (class "Default")
      (node (ref "U5") (pin "32") (pinfunction "PD2_32") (pintype "bidirectional"))
    )
    (net (code "93") (name "unconnected-(U5-PD4-Pad2)") (class "Default")
      (node (ref "U5") (pin "2") (pinfunction "PD4_2") (pintype "bidirectional"))
    )
    (net (code "94") (name "unconnected-(U12-OC-Pad3)") (class "Default")
      (node (ref "U12") (pin "3") (pinfunction "OC_3") (pintype "bidirectional"))
    )
    (net (code "95") (name "unconnected-(U12-TD-Pad4)") (class "Default")
      (node (ref "U12") (pin "4") (pinfunction "TD_4") (pintype "bidirectional"))
    )
  )
)
